# untitled.net
KiCad netlist of a schematic drawn in EAGLE
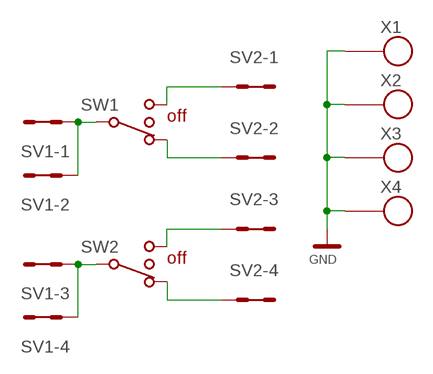
[diagram p0: schematic, sheet 1]

(export (version "E")
  (design (tool "Eeschema 10.0.6"))
  (components
    (comp (ref "SV1")
      (value "MA04-2")
      (footprint "eagle-import:MA04-2")
      (libsource (lib "eagle-import") (part "MA04-2"))
    )
    (comp (ref "SV2")
      (value "MA04-2")
      (footprint "eagle-import:MA04-2")
      (libsource (lib "eagle-import") (part "MA04-2"))
    )
    (comp (ref "SW1")
      (value "PREPINAC_POSUVNY_SL19-121")
      (footprint "eagle-import:PREPINAC-POSUVNÝ")
      (libsource (lib "eagle-import") (part "PREPINAC_POSUVNY_SL19-121"))
    )
    (comp (ref "SW2")
      (value "PREPINAC_POSUVNY_SL19-121")
      (footprint "eagle-import:PREPINAC-POSUVNÝ")
      (libsource (lib "eagle-import") (part "PREPINAC_POSUVNY_SL19-121"))
    )
    (comp (ref "X1")
      (value "SROUB3M")
      (footprint "eagle-import:SROUB3M")
      (libsource (lib "eagle-import") (part "SROUB3M"))
    )
    (comp (ref "X2")
      (value "SROUB3M")
      (footprint "eagle-import:SROUB3M")
      (libsource (lib "eagle-import") (part "SROUB3M"))
    )
    (comp (ref "X3")
      (value "SROUB3M")
      (footprint "eagle-import:SROUB3M")
      (libsource (lib "eagle-import") (part "SROUB3M"))
    )
    (comp (ref "X4")
      (value "SROUB3M")
      (footprint "eagle-import:SROUB3M")
      (libsource (lib "eagle-import") (part "SROUB3M"))
    )
  )
  (nets
    (net (code "1") (name "GND") (class "Default")
      (node (ref "X1") (pin "P$1") (pinfunction "P$1_P$1") (pintype "bidirectional"))
      (node (ref "X2") (pin "P$1") (pinfunction "P$1_P$1") (pintype "bidirectional"))
      (node (ref "X3") (pin "P$1") (pinfunction "P$1_P$1") (pintype "bidirectional"))
      (node (ref "X4") (pin "P$1") (pinfunction "P$1_P$1") (pintype "bidirectional"))
    )
    (net (code "2") (name "Net-(SV1A-K-Pad1)") (class "Default")
      (node (ref "SV1") (pin "1") (pinfunction "K_1") (pintype "passive"))
      (node (ref "SV1") (pin "2") (pinfunction "K_2") (pintype "passive"))
      (node (ref "SV1") (pin "3") (pinfunction "K_3") (pintype "passive"))
      (node (ref "SV1") (pin "4") (pinfunction "K_4") (pintype "passive"))
      (node (ref "SW1") (pin "2") (pinfunction "2_2") (pintype "passive"))
    )
    (net (code "3") (name "Net-(SV1C-K-Pad5)") (class "Default")
      (node (ref "SV1") (pin "5") (pinfunction "K_5") (pintype "passive"))
      (node (ref "SV1") (pin "6") (pinfunction "K_6") (pintype "passive"))
      (node (ref "SV1") (pin "7") (pinfunction "K_7") (pintype "passive"))
      (node (ref "SV1") (pin "8") (pinfunction "K_8") (pintype "passive"))
      (node (ref "SW2") (pin "2") (pinfunction "2_2") (pintype "passive"))
    )
    (net (code "4") (name "Net-(SW1-1)") (class "Default")
      (node (ref "SV2") (pin "1") (pinfunction "K_1") (pintype "passive"))
      (node (ref "SV2") (pin "2") (pinfunction "K_2") (pintype "passive"))
      (node (ref "SW1") (pin "3") (pinfunction "1_3") (pintype "passive"))
    )
    (net (code "5") (name "Net-(SW1-3)") (class "Default")
      (node (ref "SV2") (pin "3") (pinfunction "K_3") (pintype "passive"))
      (node (ref "SV2") (pin "4") (pinfunction "K_4") (pintype "passive"))
      (node (ref "SW1") (pin "1") (pinfunction "3_1") (pintype "passive"))
    )
    (net (code "6") (name "Net-(SW2-1)") (class "Default")
      (node (ref "SV2") (pin "5") (pinfunction "K_5") (pintype "passive"))
      (node (ref "SV2") (pin "6") (pinfunction "K_6") (pintype "passive"))
      (node (ref "SW2") (pin "3") (pinfunction "1_3") (pintype "passive"))
    )
    (net (code "7") (name "Net-(SW2-3)") (class "Default")
      (node (ref "SV2") (pin "7") (pinfunction "K_7") (pintype "passive"))
      (node (ref "SV2") (pin "8") (pinfunction "K_8") (pintype "passive"))
      (node (ref "SW2") (pin "1") (pinfunction "3_1") (pintype "passive"))
    )
  )
)
